# mainBoard.net
KiCad netlist of a schematic drawn in EAGLE
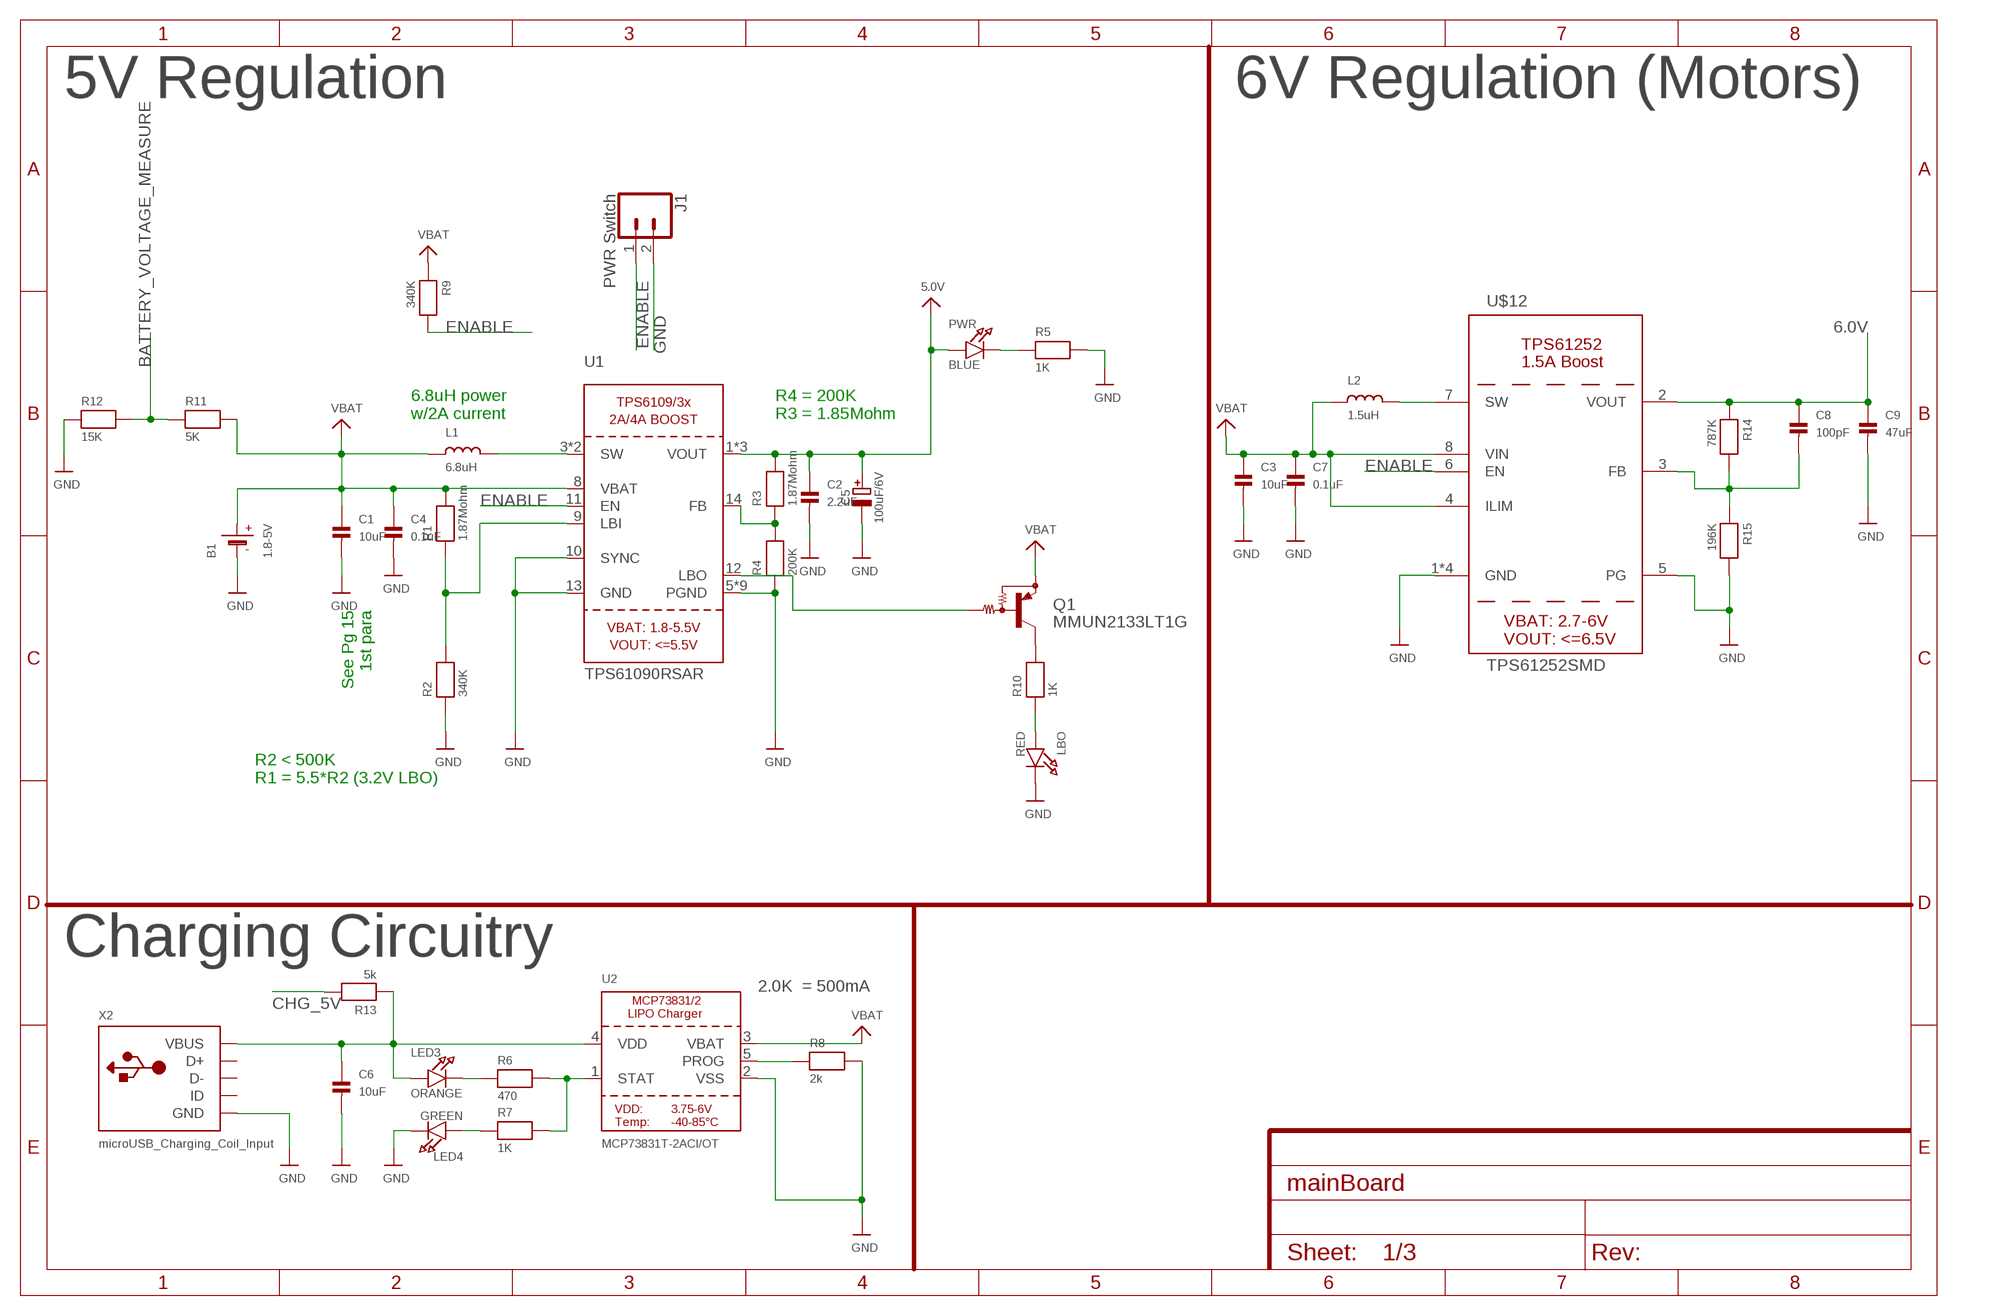
[diagram p0: schematic, sheet 1]
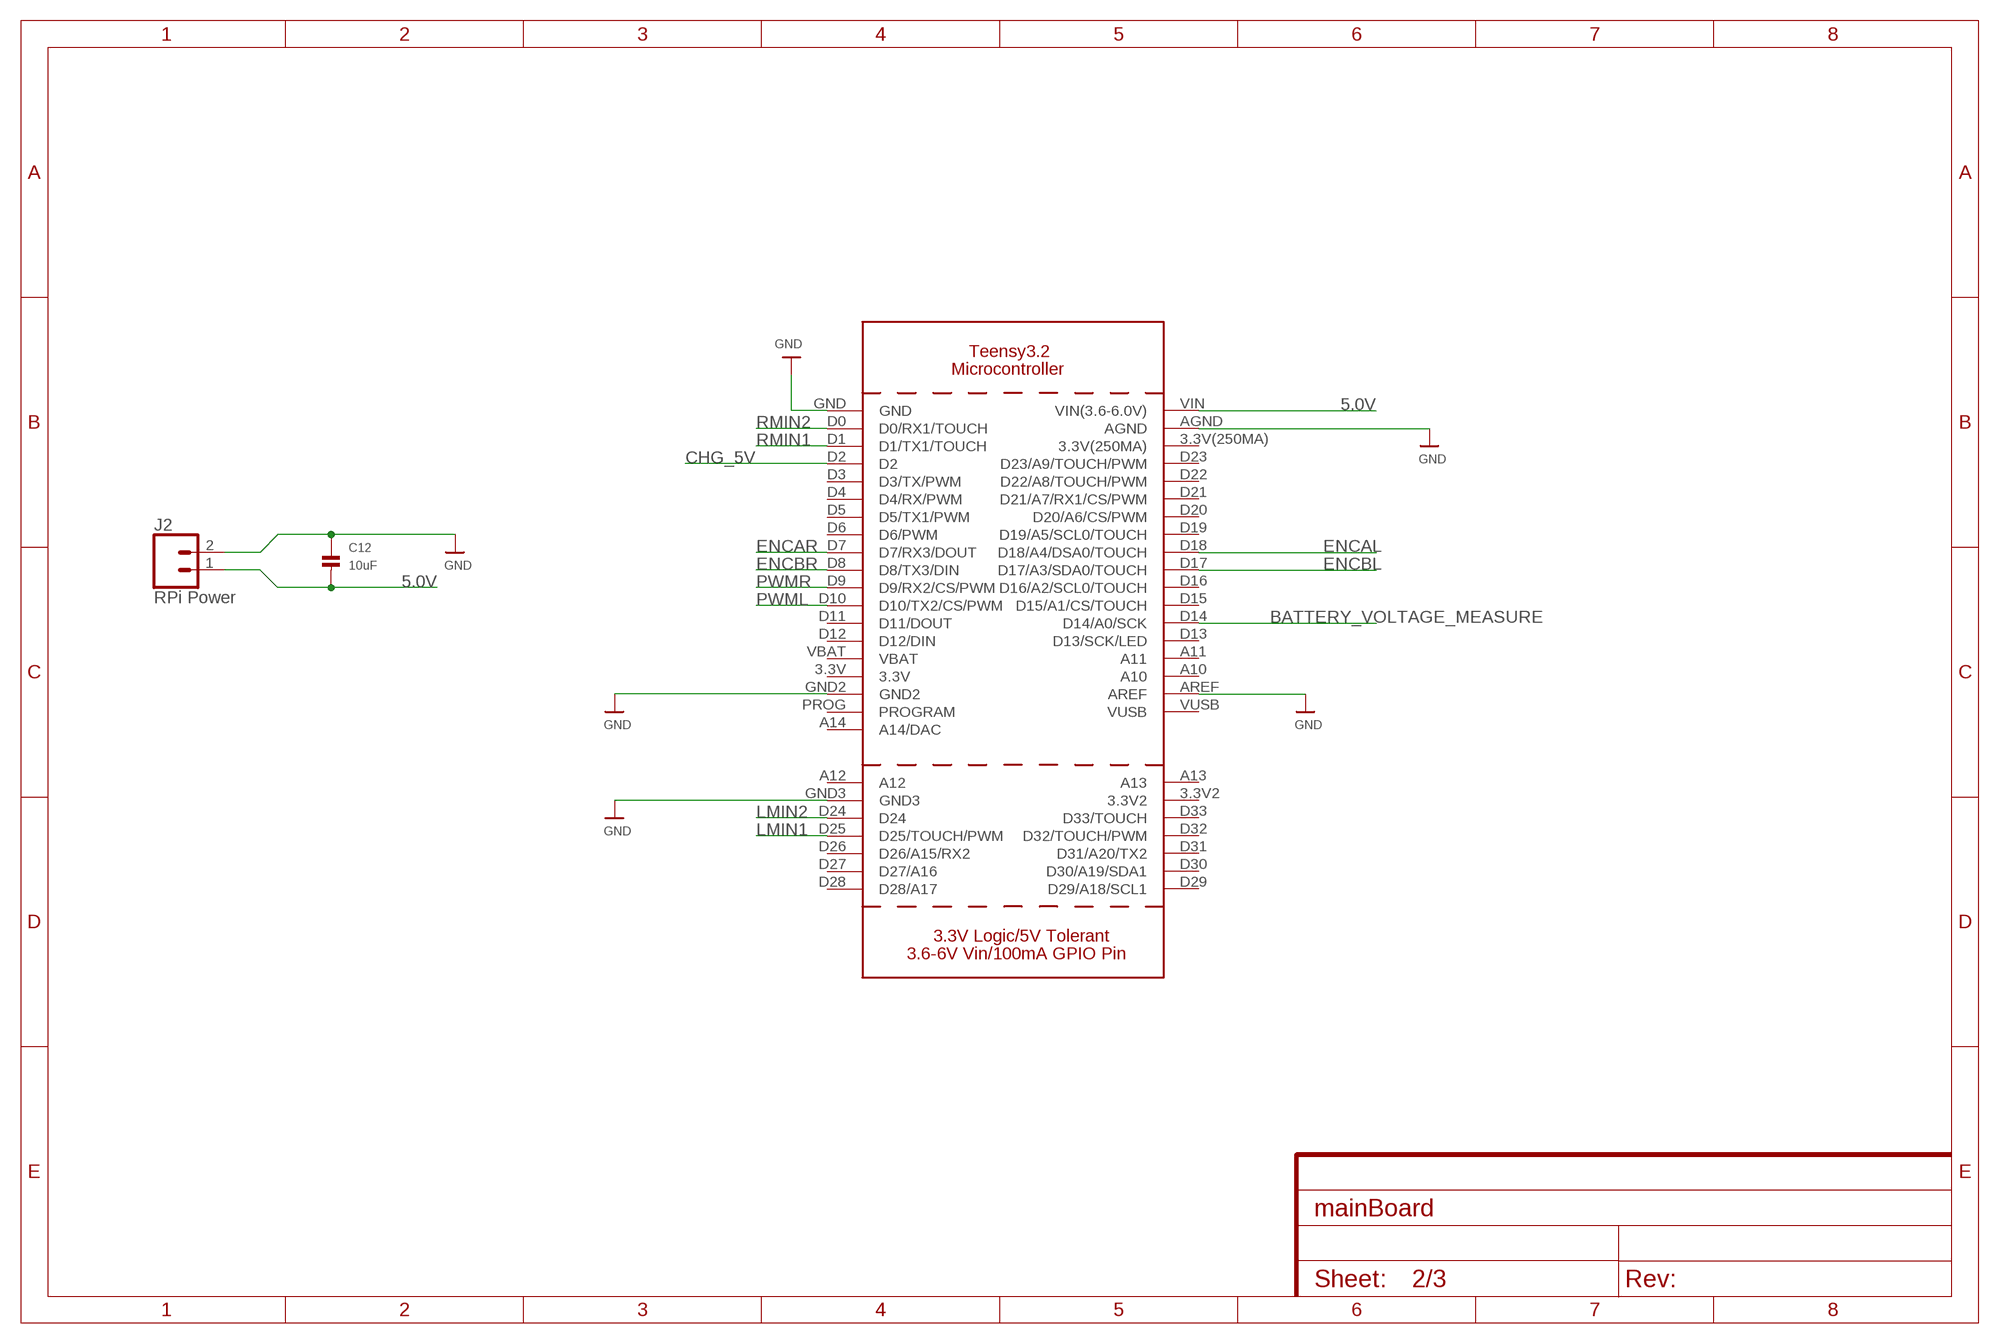
[diagram p1: schematic, sheet 2]
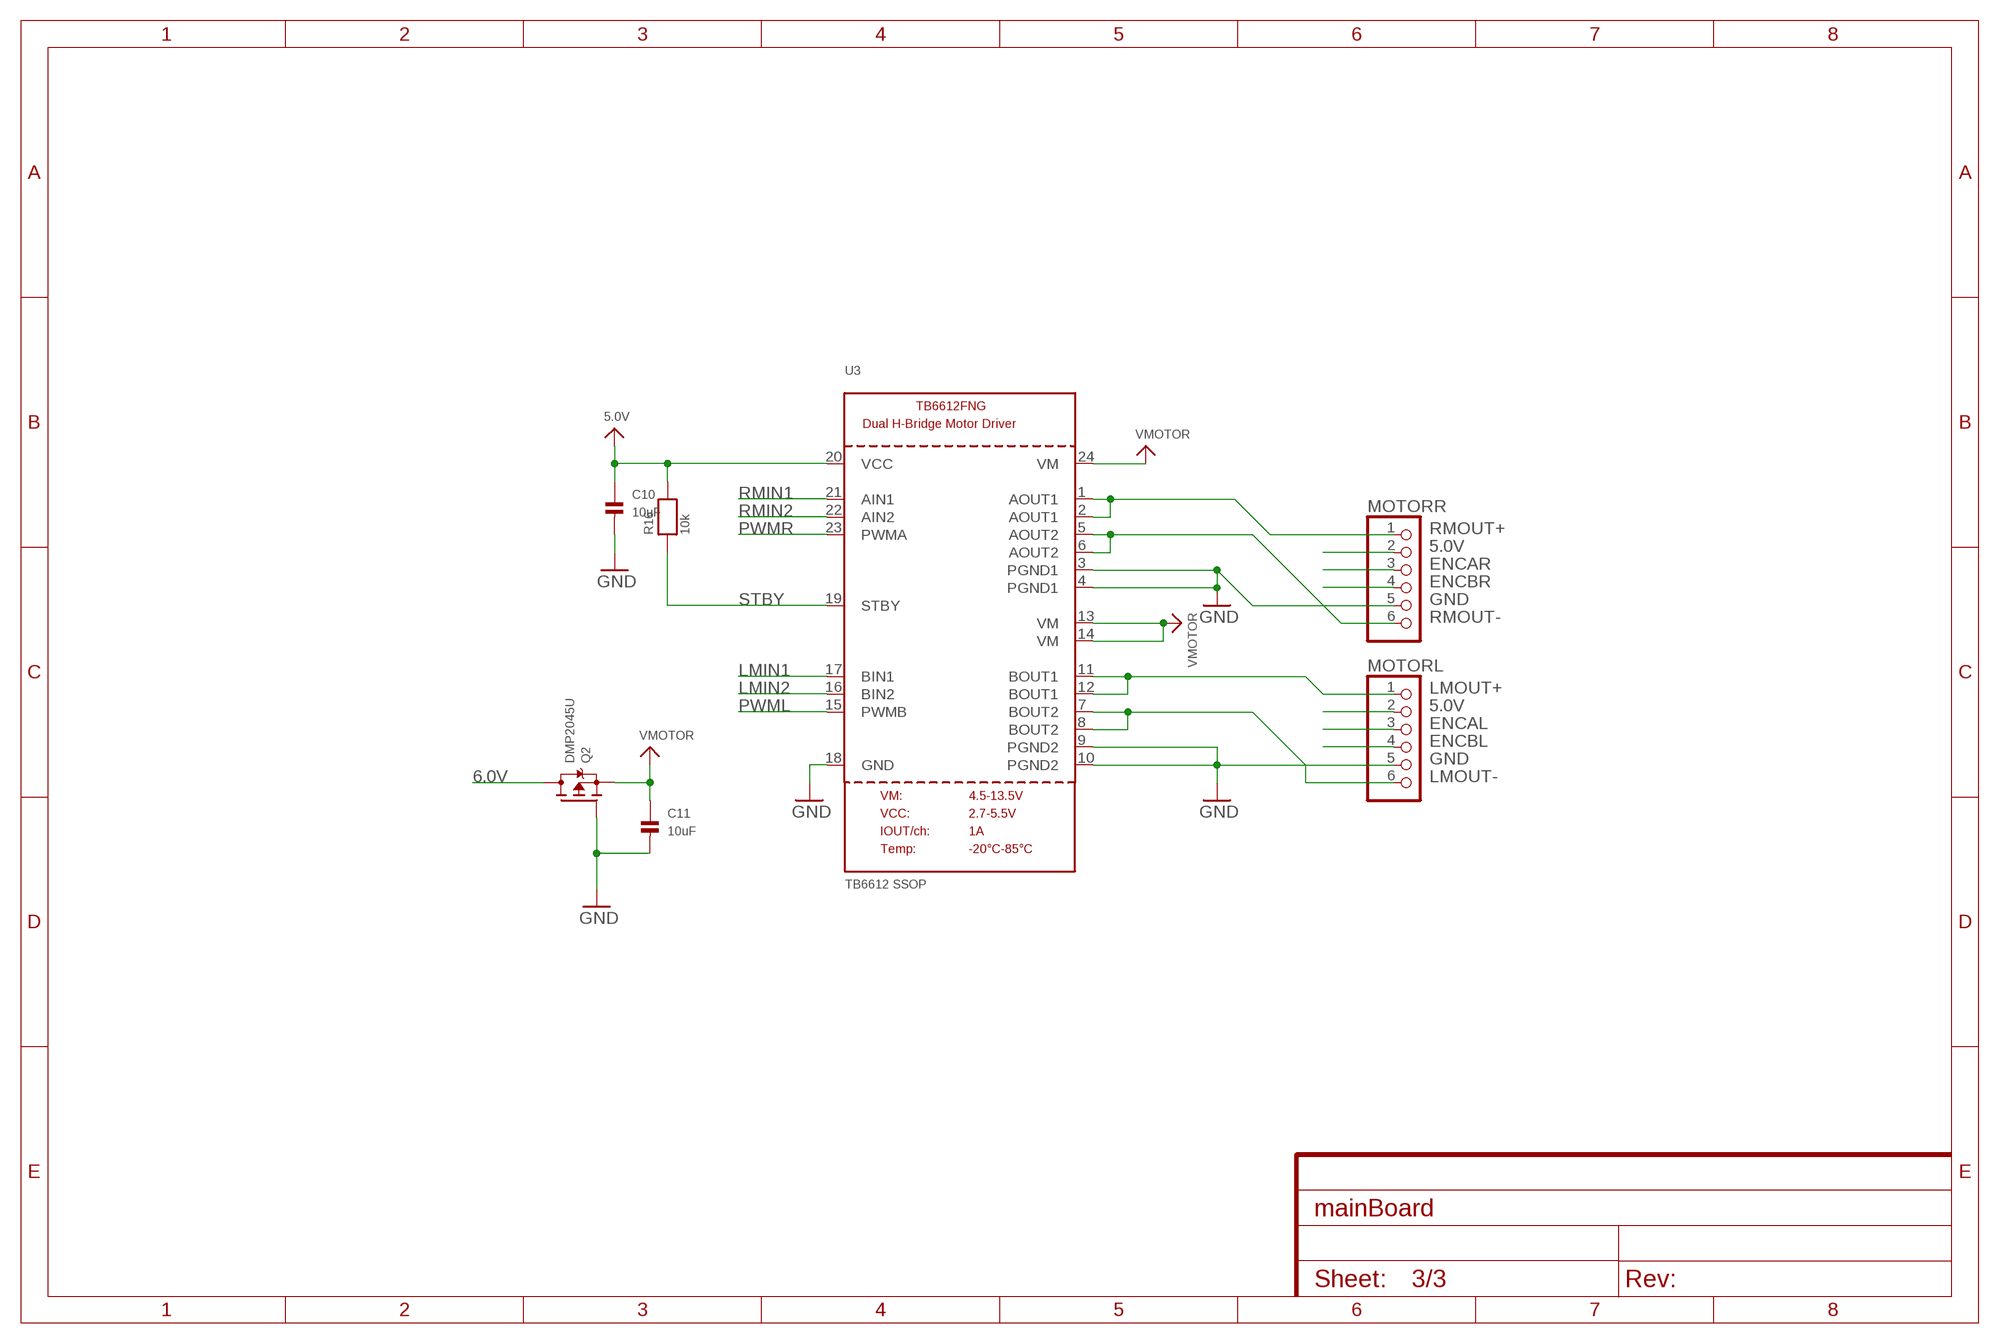
[diagram p2: schematic, sheet 3]

(export (version "E")
  (design (tool "Eeschema 10.0.6"))
  (components
    (comp (ref "C12")
      (value "10uF")
      (footprint "eagle-import:0603")
      (libsource (lib "eagle-import") (part "CAP_CERAMIC0603"))
    )
    (comp (ref "J2")
      (value "RPi Power")
      (footprint "eagle-import:1X02")
      (libsource (lib "eagle-import") (part "CONN_02"))
    )
    (comp (ref "U$28")
      (value "TEENSY3_2")
      (footprint "eagle-import:TEENSY3_2")
      (libsource (lib "eagle-import") (part "TEENSY3_2"))
    )
    (comp (ref "C10")
      (value "10uF")
      (footprint "eagle-import:0603")
      (libsource (lib "eagle-import") (part "CAP_CERAMIC0603"))
    )
    (comp (ref "C11")
      (value "10uF")
      (footprint "eagle-import:0603")
      (libsource (lib "eagle-import") (part "CAP_CERAMIC0603"))
    )
    (comp (ref "MOTORL")
      (value "PINHD-1X6CB")
      (footprint "eagle-import:1X06-CLEANBIG")
      (libsource (lib "eagle-import") (part "PINHD-1X6CB"))
    )
    (comp (ref "MOTORR")
      (value "PINHD-1X6CB")
      (footprint "eagle-import:1X06-CLEANBIG")
      (libsource (lib "eagle-import") (part "PINHD-1X6CB"))
    )
    (comp (ref "Q2")
      (value "DMP2045U")
      (footprint "eagle-import:SOT23-WIDE")
      (libsource (lib "eagle-import") (part "MOSFET-PWIDE"))
    )
    (comp (ref "R16")
      (value "10k")
      (footprint "eagle-import:0805")
      (libsource (lib "eagle-import") (part "RESISTOR0805"))
    )
    (comp (ref "U3")
      (value "TB6612 SSOP")
      (footprint "eagle-import:SSOP24")
      (libsource (lib "eagle-import") (part "TB6612FNGSSOP"))
    )
    (comp (ref "B1")
      (value "1.8-5V")
      (footprint "eagle-import:JSTPH2")
      (libsource (lib "eagle-import") (part "BATTERY"))
    )
    (comp (ref "C1")
      (value "10uF")
      (footprint "eagle-import:0603")
      (libsource (lib "eagle-import") (part "CAP_CERAMIC0603"))
    )
    (comp (ref "C2")
      (value "2.2uF")
      (footprint "eagle-import:0603")
      (libsource (lib "eagle-import") (part "CAP_CERAMIC0603"))
    )
    (comp (ref "C3")
      (value "10uF")
      (footprint "eagle-import:0603")
      (libsource (lib "eagle-import") (part "CAP_CERAMIC0603"))
    )
    (comp (ref "C4")
      (value "0.1uF")
      (footprint "eagle-import:0805")
      (libsource (lib "eagle-import") (part "CAP_CERAMIC0805"))
    )
    (comp (ref "C5")
      (value "100uF/6V")
      (footprint "eagle-import:EIA3528-21_B-R")
      (libsource (lib "eagle-import") (part "CAP_TANTALUMB/3528_REFLOW"))
    )
    (comp (ref "C6")
      (value "10uF")
      (footprint "eagle-import:0603")
      (libsource (lib "eagle-import") (part "CAP_CERAMIC0603"))
    )
    (comp (ref "C7")
      (value "0.1uF")
      (footprint "eagle-import:0805")
      (libsource (lib "eagle-import") (part "CAP_CERAMIC0805"))
    )
    (comp (ref "C8")
      (value "100pF")
      (footprint "eagle-import:0603")
      (libsource (lib "eagle-import") (part "CAP_CERAMIC0603"))
    )
    (comp (ref "C9")
      (value "47uF")
      (footprint "eagle-import:1206")
      (libsource (lib "eagle-import") (part "CAP_CERAMIC1206"))
    )
    (comp (ref "J1")
      (value "PWR Switch")
      (footprint "eagle-import:1X02")
      (libsource (lib "eagle-import") (part "CONN_02"))
    )
    (comp (ref "L1")
      (value "6.8uH")
      (footprint "eagle-import:VISHAY_IHLP2525CZER6R8M01")
      (libsource (lib "eagle-import") (part "VISHAY_IHLP2525CZER6R8M01"))
    )
    (comp (ref "L2")
      (value "1.5uH")
      (footprint "eagle-import:MURATA_DFE252012P-1R5M=P2")
      (libsource (lib "eagle-import") (part "MURATA_DFE252012P-1R5M=P2"))
    )
    (comp (ref "LBO")
      (value "RED")
      (footprint "eagle-import:CHIPLED_0805_NOOUTLINE")
      (libsource (lib "eagle-import") (part "LED0805_NOOUTLINE"))
    )
    (comp (ref "LED3")
      (value "ORANGE")
      (footprint "eagle-import:CHIPLED_0805_NOOUTLINE")
      (libsource (lib "eagle-import") (part "LED0805_NOOUTLINE"))
    )
    (comp (ref "LED4")
      (value "GREEN")
      (footprint "eagle-import:CHIPLED_0805_NOOUTLINE")
      (libsource (lib "eagle-import") (part "LED0805_NOOUTLINE"))
    )
    (comp (ref "PWR")
      (value "BLUE")
      (footprint "eagle-import:CHIPLED_0805_NOOUTLINE")
      (libsource (lib "eagle-import") (part "LED0805_NOOUTLINE"))
    )
    (comp (ref "Q1")
      (value "MMUN2133LT1G")
      (footprint "eagle-import:SC59-BEC")
      (libsource (lib "eagle-import") (part "-PNP_DRIVER-SC59-BECMUN2114T1"))
    )
    (comp (ref "R1")
      (value "1.87Mohm")
      (footprint "eagle-import:0805")
      (libsource (lib "eagle-import") (part "RESISTOR0805"))
    )
    (comp (ref "R2")
      (value "340K")
      (footprint "eagle-import:0805")
      (libsource (lib "eagle-import") (part "RESISTOR0805"))
    )
    (comp (ref "R3")
      (value "1.87Mohm")
      (footprint "eagle-import:0805")
      (libsource (lib "eagle-import") (part "RESISTOR0805"))
    )
    (comp (ref "R4")
      (value "200K")
      (footprint "eagle-import:0805")
      (libsource (lib "eagle-import") (part "RESISTOR0805"))
    )
    (comp (ref "R5")
      (value "1K")
      (footprint "eagle-import:0805")
      (libsource (lib "eagle-import") (part "RESISTOR0805"))
    )
    (comp (ref "R6")
      (value "470")
      (footprint "eagle-import:0805")
      (libsource (lib "eagle-import") (part "RESISTOR0805"))
    )
    (comp (ref "R7")
      (value "1K")
      (footprint "eagle-import:0805")
      (libsource (lib "eagle-import") (part "RESISTOR0805"))
    )
    (comp (ref "R8")
      (value "2k")
      (footprint "eagle-import:0805")
      (libsource (lib "eagle-import") (part "RESISTOR0805"))
    )
    (comp (ref "R9")
      (value "340K")
      (footprint "eagle-import:0805")
      (libsource (lib "eagle-import") (part "RESISTOR0805"))
    )
    (comp (ref "R10")
      (value "1K")
      (footprint "eagle-import:0805")
      (libsource (lib "eagle-import") (part "RESISTOR0805"))
    )
    (comp (ref "R11")
      (value "5K")
      (footprint "eagle-import:0805")
      (libsource (lib "eagle-import") (part "RESISTOR0805"))
    )
    (comp (ref "R12")
      (value "15K")
      (footprint "eagle-import:0805")
      (libsource (lib "eagle-import") (part "RESISTOR0805"))
    )
    (comp (ref "R13")
      (value "5k")
      (footprint "eagle-import:0805")
      (libsource (lib "eagle-import") (part "RESISTOR0805"))
    )
    (comp (ref "R14")
      (value "787K")
      (footprint "eagle-import:0805")
      (libsource (lib "eagle-import") (part "RESISTOR0805"))
    )
    (comp (ref "R15")
      (value "196K")
      (footprint "eagle-import:0805")
      (libsource (lib "eagle-import") (part "RESISTOR0805"))
    )
    (comp (ref "U$12")
      (value "TPS61252SMD")
      (footprint "eagle-import:TPS61252")
      (libsource (lib "eagle-import") (part "TPS61252SMD"))
    )
    (comp (ref "U1")
      (value "TPS61090RSAR")
      (footprint "eagle-import:PVQFN-16")
      (libsource (lib "eagle-import") (part "VREG_TPS6103X"))
    )
    (comp (ref "U2")
      (value "MCP73831T-2ACI/OT")
      (footprint "eagle-import:SOT23-5")
      (libsource (lib "eagle-import") (part "MCP73831/2"))
    )
    (comp (ref "X2")
      (value "microUSB_Charging_Coil_Input")
      (footprint "eagle-import:4UCONN_20329")
      (libsource (lib "eagle-import") (part "USBMICRO_20329"))
    )
  )
  (nets
    (net (code "1") (name "5.0V") (class "Default")
      (node (ref "C10") (pin "1") (pinfunction "P$1_1") (pintype "passive"))
      (node (ref "C12") (pin "2") (pinfunction "P$2_2") (pintype "passive"))
      (node (ref "C2") (pin "1") (pinfunction "P$1_1") (pintype "passive"))
      (node (ref "C5") (pin "+") (pinfunction "+_+") (pintype "passive"))
      (node (ref "J2") (pin "1") (pinfunction "1_1") (pintype "passive"))
      (node (ref "MOTORL") (pin "2") (pinfunction "2_2") (pintype "passive"))
      (node (ref "MOTORR") (pin "2") (pinfunction "2_2") (pintype "passive"))
      (node (ref "PWR") (pin "A") (pinfunction "A_A") (pintype "passive"))
      (node (ref "R16") (pin "2") (pinfunction "2_2") (pintype "passive"))
      (node (ref "R3") (pin "2") (pinfunction "2_2") (pintype "passive"))
      (node (ref "U$28") (pin "VIN") (pinfunction "VIN(3.6-6.0V)_VIN") (pintype "bidirectional"))
      (node (ref "U1") (pin "1") (pinfunction "VOUT_1") (pintype "power_in"))
      (node (ref "U1") (pin "15") (pinfunction "VOUT_15") (pintype "power_in"))
      (node (ref "U1") (pin "16") (pinfunction "VOUT_16") (pintype "power_in"))
      (node (ref "U3") (pin "20") (pinfunction "VCC_20") (pintype "power_in"))
    )
    (net (code "2") (name "6.0V") (class "Default")
      (node (ref "C8") (pin "1") (pinfunction "P$1_1") (pintype "passive"))
      (node (ref "C9") (pin "1") (pinfunction "P$1_1") (pintype "passive"))
      (node (ref "Q2") (pin "3") (pinfunction "D_3") (pintype "passive"))
      (node (ref "R14") (pin "1") (pinfunction "1_1") (pintype "passive"))
      (node (ref "U$12") (pin "2") (pinfunction "VOUT_2") (pintype "bidirectional"))
    )
    (net (code "3") (name "BATTERY_VOLTAGE_MEASURE") (class "Default")
      (node (ref "R11") (pin "1") (pinfunction "1_1") (pintype "passive"))
      (node (ref "R12") (pin "2") (pinfunction "2_2") (pintype "passive"))
      (node (ref "U$28") (pin "D14") (pinfunction "D14/A0/SCK_D14") (pintype "bidirectional"))
    )
    (net (code "4") (name "CHG_5V") (class "Default")
      (node (ref "R13") (pin "2") (pinfunction "2_2") (pintype "passive"))
      (node (ref "U$28") (pin "D2") (pinfunction "D2_D2") (pintype "bidirectional"))
    )
    (net (code "5") (name "ENABLE") (class "Default")
      (node (ref "J1") (pin "1") (pinfunction "1_1") (pintype "passive"))
      (node (ref "R9") (pin "2") (pinfunction "2_2") (pintype "passive"))
      (node (ref "U$12") (pin "6") (pinfunction "EN_6") (pintype "bidirectional"))
      (node (ref "U1") (pin "11") (pinfunction "EN_11") (pintype "input"))
    )
    (net (code "6") (name "ENCAL") (class "Default")
      (node (ref "MOTORL") (pin "3") (pinfunction "3_3") (pintype "passive"))
      (node (ref "U$28") (pin "D18") (pinfunction "D18/A4/DSA0/TOUCH_D18") (pintype "bidirectional"))
    )
    (net (code "7") (name "ENCAR") (class "Default")
      (node (ref "MOTORR") (pin "3") (pinfunction "3_3") (pintype "passive"))
      (node (ref "U$28") (pin "D7") (pinfunction "D7/RX3/DOUT_D7") (pintype "bidirectional"))
    )
    (net (code "8") (name "ENCBL") (class "Default")
      (node (ref "MOTORL") (pin "4") (pinfunction "4_4") (pintype "passive"))
      (node (ref "U$28") (pin "D17") (pinfunction "D17/A3/SDA0/TOUCH_D17") (pintype "bidirectional"))
    )
    (net (code "9") (name "ENCBR") (class "Default")
      (node (ref "MOTORR") (pin "4") (pinfunction "4_4") (pintype "passive"))
      (node (ref "U$28") (pin "D8") (pinfunction "D8/TX3/DIN_D8") (pintype "bidirectional"))
    )
    (net (code "10") (name "GND") (class "Default")
      (node (ref "B1") (pin "1") (pinfunction "-_1") (pintype "passive"))
      (node (ref "C1") (pin "2") (pinfunction "P$2_2") (pintype "passive"))
      (node (ref "C10") (pin "2") (pinfunction "P$2_2") (pintype "passive"))
      (node (ref "C11") (pin "2") (pinfunction "P$2_2") (pintype "passive"))
      (node (ref "C12") (pin "1") (pinfunction "P$1_1") (pintype "passive"))
      (node (ref "C2") (pin "2") (pinfunction "P$2_2") (pintype "passive"))
      (node (ref "C3") (pin "2") (pinfunction "P$2_2") (pintype "passive"))
      (node (ref "C4") (pin "2") (pinfunction "P$2_2") (pintype "passive"))
      (node (ref "C5") (pin "-") (pinfunction "-_-") (pintype "passive"))
      (node (ref "C6") (pin "2") (pinfunction "P$2_2") (pintype "passive"))
      (node (ref "C7") (pin "2") (pinfunction "P$2_2") (pintype "passive"))
      (node (ref "C9") (pin "2") (pinfunction "P$2_2") (pintype "passive"))
      (node (ref "J1") (pin "2") (pinfunction "2_2") (pintype "passive"))
      (node (ref "J2") (pin "2") (pinfunction "2_2") (pintype "passive"))
      (node (ref "LBO") (pin "C") (pinfunction "C_C") (pintype "passive"))
      (node (ref "LED4") (pin "C") (pinfunction "C_C") (pintype "passive"))
      (node (ref "MOTORL") (pin "5") (pinfunction "5_5") (pintype "passive"))
      (node (ref "MOTORR") (pin "5") (pinfunction "5_5") (pintype "passive"))
      (node (ref "Q2") (pin "1") (pinfunction "G_1") (pintype "passive"))
      (node (ref "R12") (pin "1") (pinfunction "1_1") (pintype "passive"))
      (node (ref "R15") (pin "2") (pinfunction "2_2") (pintype "passive"))
      (node (ref "R2") (pin "1") (pinfunction "1_1") (pintype "passive"))
      (node (ref "R4") (pin "1") (pinfunction "1_1") (pintype "passive"))
      (node (ref "R5") (pin "2") (pinfunction "2_2") (pintype "passive"))
      (node (ref "R8") (pin "2") (pinfunction "2_2") (pintype "passive"))
      (node (ref "U$12") (pin "1") (pinfunction "GND_1") (pintype "bidirectional"))
      (node (ref "U$12") (pin "5") (pinfunction "PG_5") (pintype "bidirectional"))
      (node (ref "U$12") (pin "P$2_GND") (pinfunction "GND_P$2_GND") (pintype "bidirectional"))
      (node (ref "U$12") (pin "P$3_GND") (pinfunction "GND_P$3_GND") (pintype "bidirectional"))
      (node (ref "U$12") (pin "THERMAL_GND") (pinfunction "GND_THERMAL_GND") (pintype "bidirectional"))
      (node (ref "U$28") (pin "AGND") (pinfunction "AGND_AGND") (pintype "bidirectional"))
      (node (ref "U$28") (pin "AREF") (pinfunction "AREF_AREF") (pintype "bidirectional"))
      (node (ref "U$28") (pin "GND") (pinfunction "GND_GND") (pintype "bidirectional"))
      (node (ref "U$28") (pin "GND2") (pinfunction "GND2_GND2") (pintype "bidirectional"))
      (node (ref "U$28") (pin "GND3") (pinfunction "GND3_GND3") (pintype "bidirectional"))
      (node (ref "U1") (pin "10") (pinfunction "SYNC_10") (pintype "input"))
      (node (ref "U1") (pin "13") (pinfunction "GND_13") (pintype "power_in"))
      (node (ref "U1") (pin "5") (pinfunction "PGND_5") (pintype "power_in"))
      (node (ref "U1") (pin "6") (pinfunction "PGND_6") (pintype "power_in"))
      (node (ref "U1") (pin "7") (pinfunction "PGND_7") (pintype "power_in"))
      (node (ref "U1") (pin "P$18") (pinfunction "PGND_P$18") (pintype "power_in"))
      (node (ref "U1") (pin "P$19") (pinfunction "PGND_P$19") (pintype "power_in"))
      (node (ref "U1") (pin "P$20") (pinfunction "PGND_P$20") (pintype "power_in"))
      (node (ref "U1") (pin "P$21") (pinfunction "PGND_P$21") (pintype "power_in"))
      (node (ref "U1") (pin "P$22") (pinfunction "PGND_P$22") (pintype "power_in"))
      (node (ref "U1") (pin "THERMAL") (pinfunction "PGND_THERMAL") (pintype "power_in"))
      (node (ref "U2") (pin "2") (pinfunction "VSS_2") (pintype "power_in"))
      (node (ref "U3") (pin "10") (pinfunction "PGND2_10") (pintype "power_in"))
      (node (ref "U3") (pin "18") (pinfunction "GND_18") (pintype "power_in"))
      (node (ref "U3") (pin "3") (pinfunction "PGND1_3") (pintype "power_in"))
      (node (ref "U3") (pin "4") (pinfunction "PGND1_4") (pintype "power_in"))
      (node (ref "U3") (pin "9") (pinfunction "PGND2_9") (pintype "power_in"))
      (node (ref "X2") (pin "BASE@1") (pinfunction "GND_BASE@1") (pintype "power_in"))
      (node (ref "X2") (pin "BASE@2") (pinfunction "GND_BASE@2") (pintype "power_in"))
      (node (ref "X2") (pin "GND") (pinfunction "GND_GND") (pintype "power_in"))
      (node (ref "X2") (pin "SPRT@1") (pinfunction "GND_SPRT@1") (pintype "power_in"))
      (node (ref "X2") (pin "SPRT@2") (pinfunction "GND_SPRT@2") (pintype "power_in"))
      (node (ref "X2") (pin "SPRT@3") (pinfunction "GND_SPRT@3") (pintype "power_in"))
      (node (ref "X2") (pin "SPRT@4") (pinfunction "GND_SPRT@4") (pintype "power_in"))
    )
    (net (code "11") (name "LMIN1") (class "Default")
      (node (ref "U$28") (pin "D25") (pinfunction "D25/TOUCH/PWM_D25") (pintype "bidirectional"))
      (node (ref "U3") (pin "17") (pinfunction "BIN1_17") (pintype "input"))
    )
    (net (code "12") (name "LMIN2") (class "Default")
      (node (ref "U$28") (pin "D24") (pinfunction "D24_D24") (pintype "bidirectional"))
      (node (ref "U3") (pin "16") (pinfunction "BIN2_16") (pintype "input"))
    )
    (net (code "13") (name "LMOUT+") (class "Default")
      (node (ref "MOTORL") (pin "1") (pinfunction "1_1") (pintype "passive"))
      (node (ref "U3") (pin "11") (pinfunction "BOUT1_11") (pintype "output"))
      (node (ref "U3") (pin "12") (pinfunction "BOUT1_12") (pintype "output"))
    )
    (net (code "14") (name "LMOUT-") (class "Default")
      (node (ref "MOTORL") (pin "6") (pinfunction "6_6") (pintype "passive"))
      (node (ref "U3") (pin "7") (pinfunction "BOUT2_7") (pintype "output"))
      (node (ref "U3") (pin "8") (pinfunction "BOUT2_8") (pintype "output"))
    )
    (net (code "15") (name "Net-(C6-P$1)") (class "Default")
      (node (ref "C6") (pin "1") (pinfunction "P$1_1") (pintype "passive"))
      (node (ref "LED3") (pin "A") (pinfunction "A_A") (pintype "passive"))
      (node (ref "R13") (pin "1") (pinfunction "1_1") (pintype "passive"))
      (node (ref "U2") (pin "4") (pinfunction "VDD_4") (pintype "power_in"))
      (node (ref "X2") (pin "VBUS") (pinfunction "VBUS_VBUS") (pintype "power_in"))
    )
    (net (code "16") (name "Net-(C8-P$2)") (class "Default")
      (node (ref "C8") (pin "2") (pinfunction "P$2_2") (pintype "passive"))
      (node (ref "R14") (pin "2") (pinfunction "2_2") (pintype "passive"))
      (node (ref "R15") (pin "1") (pinfunction "1_1") (pintype "passive"))
      (node (ref "U$12") (pin "3") (pinfunction "FB_3") (pintype "bidirectional"))
    )
    (net (code "17") (name "Net-(L1-2)") (class "Default")
      (node (ref "L1") (pin "P$2") (pinfunction "2_P$2") (pintype "passive"))
      (node (ref "U1") (pin "3") (pinfunction "SW_3") (pintype "input"))
      (node (ref "U1") (pin "4") (pinfunction "SW_4") (pintype "input"))
    )
    (net (code "18") (name "Net-(L2-2)") (class "Default")
      (node (ref "L2") (pin "P$2") (pinfunction "2_P$2") (pintype "passive"))
      (node (ref "U$12") (pin "7") (pinfunction "SW_7") (pintype "bidirectional"))
    )
    (net (code "19") (name "Net-(LBO-PadA)") (class "Default")
      (node (ref "LBO") (pin "A") (pinfunction "A_A") (pintype "passive"))
      (node (ref "R10") (pin "1") (pinfunction "1_1") (pintype "passive"))
    )
    (net (code "20") (name "Net-(LED3-PadC)") (class "Default")
      (node (ref "LED3") (pin "C") (pinfunction "C_C") (pintype "passive"))
      (node (ref "R6") (pin "1") (pinfunction "1_1") (pintype "passive"))
    )
    (net (code "21") (name "Net-(LED4-PadA)") (class "Default")
      (node (ref "LED4") (pin "A") (pinfunction "A_A") (pintype "passive"))
      (node (ref "R7") (pin "1") (pinfunction "1_1") (pintype "passive"))
    )
    (net (code "22") (name "Net-(PWR-PadC)") (class "Default")
      (node (ref "PWR") (pin "C") (pinfunction "C_C") (pintype "passive"))
      (node (ref "R5") (pin "1") (pinfunction "1_1") (pintype "passive"))
    )
    (net (code "23") (name "Net-(Q1-PadC)") (class "Default")
      (node (ref "Q1") (pin "C") (pinfunction "C_C") (pintype "passive"))
      (node (ref "R10") (pin "2") (pinfunction "2_2") (pintype "passive"))
    )
    (net (code "24") (name "Net-(U1-FB)") (class "Default")
      (node (ref "R3") (pin "1") (pinfunction "1_1") (pintype "passive"))
      (node (ref "R4") (pin "2") (pinfunction "2_2") (pintype "passive"))
      (node (ref "U1") (pin "14") (pinfunction "FB_14") (pintype "input"))
    )
    (net (code "25") (name "Net-(U1-LBI)") (class "Default")
      (node (ref "R1") (pin "1") (pinfunction "1_1") (pintype "passive"))
      (node (ref "R2") (pin "2") (pinfunction "2_2") (pintype "passive"))
      (node (ref "U1") (pin "9") (pinfunction "LBI_9") (pintype "input"))
    )
    (net (code "26") (name "Net-(U1-LBO)") (class "Default")
      (node (ref "Q1") (pin "B") (pinfunction "B_B") (pintype "passive"))
      (node (ref "U1") (pin "12") (pinfunction "LBO_12") (pintype "output"))
    )
    (net (code "27") (name "Net-(U2-PROG)") (class "Default")
      (node (ref "R8") (pin "1") (pinfunction "1_1") (pintype "passive"))
      (node (ref "U2") (pin "5") (pinfunction "PROG_5") (pintype "input"))
    )
    (net (code "28") (name "Net-(U2-STAT)") (class "Default")
      (node (ref "R6") (pin "2") (pinfunction "2_2") (pintype "passive"))
      (node (ref "R7") (pin "2") (pinfunction "2_2") (pintype "passive"))
      (node (ref "U2") (pin "1") (pinfunction "STAT_1") (pintype "output"))
    )
    (net (code "29") (name "PWML") (class "Default")
      (node (ref "U$28") (pin "D10") (pinfunction "D10/TX2/CS/PWM_D10") (pintype "bidirectional"))
      (node (ref "U3") (pin "15") (pinfunction "PWMB_15") (pintype "input"))
    )
    (net (code "30") (name "PWMR") (class "Default")
      (node (ref "U$28") (pin "D9") (pinfunction "D9/RX2/CS/PWM_D9") (pintype "bidirectional"))
      (node (ref "U3") (pin "23") (pinfunction "PWMA_23") (pintype "input"))
    )
    (net (code "31") (name "RMIN1") (class "Default")
      (node (ref "U$28") (pin "D1") (pinfunction "D1/TX1/TOUCH_D1") (pintype "bidirectional"))
      (node (ref "U3") (pin "21") (pinfunction "AIN1_21") (pintype "input"))
    )
    (net (code "32") (name "RMIN2") (class "Default")
      (node (ref "U$28") (pin "D0") (pinfunction "D0/RX1/TOUCH_D0") (pintype "bidirectional"))
      (node (ref "U3") (pin "22") (pinfunction "AIN2_22") (pintype "input"))
    )
    (net (code "33") (name "RMOUT+") (class "Default")
      (node (ref "MOTORR") (pin "1") (pinfunction "1_1") (pintype "passive"))
      (node (ref "U3") (pin "1") (pinfunction "AOUT1_1") (pintype "output"))
      (node (ref "U3") (pin "2") (pinfunction "AOUT1_2") (pintype "output"))
    )
    (net (code "34") (name "RMOUT-") (class "Default")
      (node (ref "MOTORR") (pin "6") (pinfunction "6_6") (pintype "passive"))
      (node (ref "U3") (pin "5") (pinfunction "AOUT2_5") (pintype "output"))
      (node (ref "U3") (pin "6") (pinfunction "AOUT2_6") (pintype "output"))
    )
    (net (code "35") (name "STBY") (class "Default")
      (node (ref "R16") (pin "1") (pinfunction "1_1") (pintype "passive"))
      (node (ref "U3") (pin "19") (pinfunction "STBY_19") (pintype "input"))
    )
    (net (code "36") (name "VBAT") (class "Default")
      (node (ref "B1") (pin "2") (pinfunction "+_2") (pintype "passive"))
      (node (ref "C1") (pin "1") (pinfunction "P$1_1") (pintype "passive"))
      (node (ref "C3") (pin "1") (pinfunction "P$1_1") (pintype "passive"))
      (node (ref "C4") (pin "1") (pinfunction "P$1_1") (pintype "passive"))
      (node (ref "C7") (pin "1") (pinfunction "P$1_1") (pintype "passive"))
      (node (ref "L1") (pin "P$1") (pinfunction "1_P$1") (pintype "passive"))
      (node (ref "L2") (pin "P$1") (pinfunction "1_P$1") (pintype "passive"))
      (node (ref "Q1") (pin "E") (pinfunction "E_E") (pintype "passive"))
      (node (ref "R1") (pin "2") (pinfunction "2_2") (pintype "passive"))
      (node (ref "R11") (pin "2") (pinfunction "2_2") (pintype "passive"))
      (node (ref "R9") (pin "1") (pinfunction "1_1") (pintype "passive"))
      (node (ref "U$12") (pin "4") (pinfunction "ILIM_4") (pintype "bidirectional"))
      (node (ref "U$12") (pin "8") (pinfunction "VIN_8") (pintype "bidirectional"))
      (node (ref "U1") (pin "8") (pinfunction "VBAT_8") (pintype "input"))
      (node (ref "U2") (pin "3") (pinfunction "VBAT_3") (pintype "power_in"))
    )
    (net (code "37") (name "VMOTOR") (class "Default")
      (node (ref "C11") (pin "1") (pinfunction "P$1_1") (pintype "passive"))
      (node (ref "Q2") (pin "2") (pinfunction "S_2") (pintype "passive"))
      (node (ref "U3") (pin "13") (pinfunction "VM_13") (pintype "power_in"))
      (node (ref "U3") (pin "14") (pinfunction "VM_14") (pintype "power_in"))
      (node (ref "U3") (pin "24") (pinfunction "VM_24") (pintype "power_in"))
    )
    (net (code "38") (name "unconnected-(U$28-A14{slash}DAC-PadA14)") (class "Default")
      (node (ref "U$28") (pin "A14") (pinfunction "A14/DAC_A14") (pintype "bidirectional"))
    )
    (net (code "39") (name "unconnected-(U$28-D3{slash}TX{slash}PWM-PadD3)") (class "Default")
      (node (ref "U$28") (pin "D3") (pinfunction "D3/TX/PWM_D3") (pintype "bidirectional"))
    )
    (net (code "40") (name "unconnected-(U$28-D4{slash}RX{slash}PWM-PadD4)") (class "Default")
      (node (ref "U$28") (pin "D4") (pinfunction "D4/RX/PWM_D4") (pintype "bidirectional"))
    )
    (net (code "41") (name "unconnected-(U$28-D5{slash}TX1{slash}PWM-PadD5)") (class "Default")
      (node (ref "U$28") (pin "D5") (pinfunction "D5/TX1/PWM_D5") (pintype "bidirectional"))
    )
    (net (code "42") (name "unconnected-(U$28-D6{slash}PWM-PadD6)") (class "Default")
      (node (ref "U$28") (pin "D6") (pinfunction "D6/PWM_D6") (pintype "bidirectional"))
    )
    (net (code "43") (name "unconnected-(U$28-D11{slash}DOUT-PadD11)") (class "Default")
      (node (ref "U$28") (pin "D11") (pinfunction "D11/DOUT_D11") (pintype "bidirectional"))
    )
    (net (code "44") (name "unconnected-(U$28-D12{slash}DIN-PadD12)") (class "Default")
      (node (ref "U$28") (pin "D12") (pinfunction "D12/DIN_D12") (pintype "bidirectional"))
    )
    (net (code "45") (name "unconnected-(U$28-D13{slash}SCK{slash}LED-PadD13)") (class "Default")
      (node (ref "U$28") (pin "D13") (pinfunction "D13/SCK/LED_D13") (pintype "bidirectional"))
    )
    (net (code "46") (name "unconnected-(U$28-D15{slash}A1{slash}CS{slash}TOUCH-PadD15)") (class "Default")
      (node (ref "U$28") (pin "D15") (pinfunction "D15/A1/CS/TOUCH_D15") (pintype "bidirectional"))
    )
    (net (code "47") (name "unconnected-(U$28-D16{slash}A2{slash}SCL0{slash}TOUCH-PadD16)") (class "Default")
      (node (ref "U$28") (pin "D16") (pinfunction "D16/A2/SCL0/TOUCH_D16") (pintype "bidirectional"))
    )
    (net (code "48") (name "unconnected-(U$28-D19{slash}A5{slash}SCL0{slash}TOUCH-PadD19)") (class "Default")
      (node (ref "U$28") (pin "D19") (pinfunction "D19/A5/SCL0/TOUCH_D19") (pintype "bidirectional"))
    )
    (net (code "49") (name "unconnected-(U$28-D20{slash}A6{slash}CS{slash}PWM-PadD20)") (class "Default")
      (node (ref "U$28") (pin "D20") (pinfunction "D20/A6/CS/PWM_D20") (pintype "bidirectional"))
    )
    (net (code "50") (name "unconnected-(U$28-D21{slash}A7{slash}RX1{slash}CS{slash}PWM-PadD21)") (class "Default")
      (node (ref "U$28") (pin "D21") (pinfunction "D21/A7/RX1/CS/PWM_D21") (pintype "bidirectional"))
    )
    (net (code "51") (name "unconnected-(U$28-D22{slash}A8{slash}TOUCH{slash}PWM-PadD22)") (class "Default")
      (node (ref "U$28") (pin "D22") (pinfunction "D22/A8/TOUCH/PWM_D22") (pintype "bidirectional"))
    )
    (net (code "52") (name "unconnected-(U$28-D23{slash}A9{slash}TOUCH{slash}PWM-PadD23)") (class "Default")
      (node (ref "U$28") (pin "D23") (pinfunction "D23/A9/TOUCH/PWM_D23") (pintype "bidirectional"))
    )
    (net (code "53") (name "unconnected-(U$28-D26{slash}A15{slash}RX2-PadD26)") (class "Default")
      (node (ref "U$28") (pin "D26") (pinfunction "D26/A15/RX2_D26") (pintype "bidirectional"))
    )
    (net (code "54") (name "unconnected-(U$28-D27{slash}A16-PadD27)") (class "Default")
      (node (ref "U$28") (pin "D27") (pinfunction "D27/A16_D27") (pintype "bidirectional"))
    )
    (net (code "55") (name "unconnected-(U$28-D28{slash}A17-PadD28)") (class "Default")
      (node (ref "U$28") (pin "D28") (pinfunction "D28/A17_D28") (pintype "bidirectional"))
    )
    (net (code "56") (name "unconnected-(U$28-D29{slash}A18{slash}SCL1-PadD29)") (class "Default")
      (node (ref "U$28") (pin "D29") (pinfunction "D29/A18/SCL1_D29") (pintype "bidirectional"))
    )
    (net (code "57") (name "unconnected-(U$28-D30{slash}A19{slash}SDA1-PadD30)") (class "Default")
      (node (ref "U$28") (pin "D30") (pinfunction "D30/A19/SDA1_D30") (pintype "bidirectional"))
    )
    (net (code "58") (name "unconnected-(U$28-D31{slash}A20{slash}TX2-PadD31)") (class "Default")
      (node (ref "U$28") (pin "D31") (pinfunction "D31/A20/TX2_D31") (pintype "bidirectional"))
    )
    (net (code "59") (name "unconnected-(U$28-D32{slash}TOUCH{slash}PWM-PadD32)") (class "Default")
      (node (ref "U$28") (pin "D32") (pinfunction "D32/TOUCH/PWM_D32") (pintype "bidirectional"))
    )
    (net (code "60") (name "unconnected-(U$28-D33{slash}TOUCH-PadD33)") (class "Default")
      (node (ref "U$28") (pin "D33") (pinfunction "D33/TOUCH_D33") (pintype "bidirectional"))
    )
    (net (code "61") (name "unconnected-(U$28-PROGRAM-PadPROG)") (class "Default")
      (node (ref "U$28") (pin "PROG") (pinfunction "PROGRAM_PROG") (pintype "bidirectional"))
    )
    (net (code "62") (name "unconnected-(U$28-Pad3.3V(250MA))") (class "Default")
      (node (ref "U$28") (pin "3.3V(250MA)") (pinfunction "3.3V(250MA)_3.3V(250MA)") (pintype "bidirectional"))
    )
    (net (code "63") (name "unconnected-(U$28-Pad3.3V)") (class "Default")
      (node (ref "U$28") (pin "3.3V") (pinfunction "3.3V_3.3V") (pintype "bidirectional"))
    )
    (net (code "64") (name "unconnected-(U$28-Pad3.3V2)") (class "Default")
      (node (ref "U$28") (pin "3.3V2") (pinfunction "3.3V2_3.3V2") (pintype "bidirectional"))
    )
    (net (code "65") (name "unconnected-(U$28-PadA10)") (class "Default")
      (node (ref "U$28") (pin "A10") (pinfunction "A10_A10") (pintype "bidirectional"))
    )
    (net (code "66") (name "unconnected-(U$28-PadA11)") (class "Default")
      (node (ref "U$28") (pin "A11") (pinfunction "A11_A11") (pintype "bidirectional"))
    )
    (net (code "67") (name "unconnected-(U$28-PadA12)") (class "Default")
      (node (ref "U$28") (pin "A12") (pinfunction "A12_A12") (pintype "bidirectional"))
    )
    (net (code "68") (name "unconnected-(U$28-PadA13)") (class "Default")
      (node (ref "U$28") (pin "A13") (pinfunction "A13_A13") (pintype "bidirectional"))
    )
    (net (code "69") (name "unconnected-(U$28-PadVBAT)") (class "Default")
      (node (ref "U$28") (pin "VBAT") (pinfunction "VBAT_VBAT") (pintype "bidirectional"))
    )
    (net (code "70") (name "unconnected-(U$28-PadVUSB)") (class "Default")
      (node (ref "U$28") (pin "VUSB") (pinfunction "VUSB_VUSB") (pintype "bidirectional"))
    )
    (net (code "71") (name "unconnected-(X2-PadD+)") (class "Default")
      (node (ref "X2") (pin "D+") (pinfunction "D+_D+") (pintype "bidirectional"))
    )
    (net (code "72") (name "unconnected-(X2-PadD-)") (class "Default")
      (node (ref "X2") (pin "D-") (pinfunction "D-_D-") (pintype "bidirectional"))
    )
    (net (code "73") (name "unconnected-(X2-PadID)") (class "Default")
      (node (ref "X2") (pin "ID") (pinfunction "ID_ID") (pintype "bidirectional"))
    )
  )
)
